# nano2_dps310.net
KiCad netlist of a schematic drawn in EAGLE
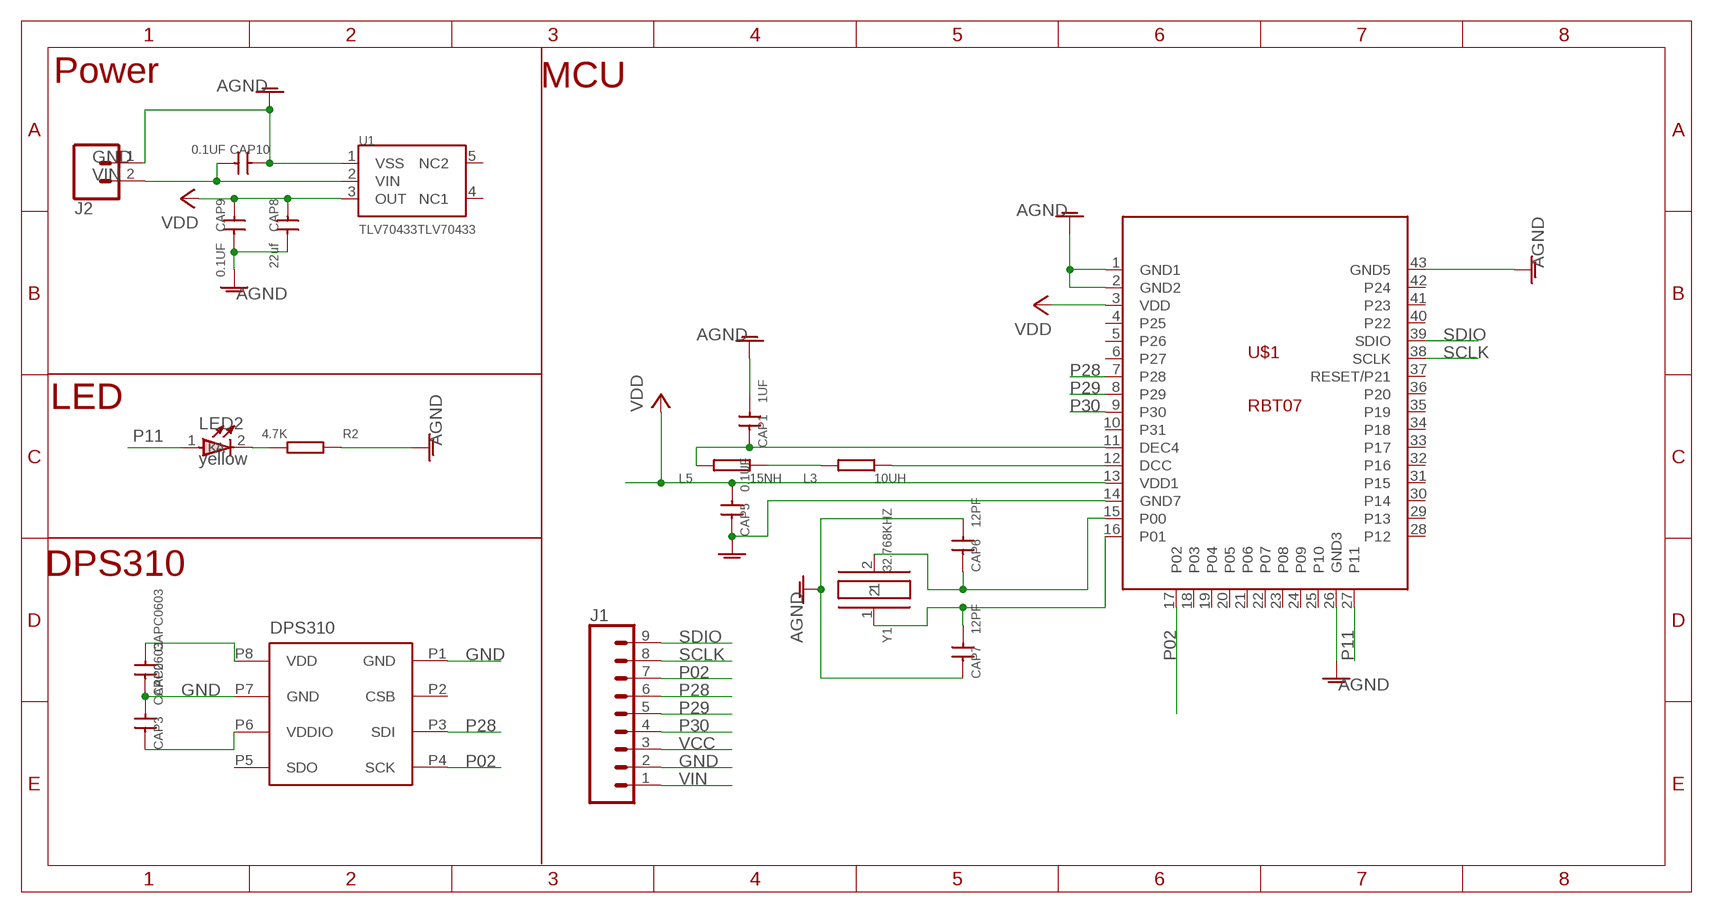
[diagram p0: schematic, sheet 1]

(export (version "E")
  (design (tool "Eeschema 10.0.6"))
  (components
    (comp (ref "CAP1")
      (value "1UF")
      (footprint "eagle-import:C-0402")
      (libsource (lib "eagle-import") (part "NANO2_CAP0402"))
    )
    (comp (ref "CAP2")
      (value "CAPC0603")
      (footprint "eagle-import:C0603")
      (libsource (lib "eagle-import") (part "CAPC0603"))
    )
    (comp (ref "CAP3")
      (value "CAPC0603")
      (footprint "eagle-import:C0603")
      (libsource (lib "eagle-import") (part "CAPC0603"))
    )
    (comp (ref "CAP5")
      (value "0.1UF")
      (footprint "eagle-import:C-0402")
      (libsource (lib "eagle-import") (part "NANO2_CAP0402"))
    )
    (comp (ref "CAP6")
      (value "12PF")
      (footprint "eagle-import:C-0402")
      (libsource (lib "eagle-import") (part "NANO2_CAP0402"))
    )
    (comp (ref "CAP7")
      (value "12PF")
      (footprint "eagle-import:C-0402")
      (libsource (lib "eagle-import") (part "NANO2_CAP0402"))
    )
    (comp (ref "CAP8")
      (value "22uf")
      (footprint "eagle-import:C0805")
      (libsource (lib "eagle-import") (part "NANO2_CAPC0805"))
    )
    (comp (ref "CAP9")
      (value "0.1UF")
      (footprint "eagle-import:C-0402")
      (libsource (lib "eagle-import") (part "NANO2_CAP0402"))
    )
    (comp (ref "CAP10")
      (value "0.1UF")
      (footprint "eagle-import:C-0402")
      (libsource (lib "eagle-import") (part "CAP0402"))
    )
    (comp (ref "J1")
      (value "CONN_09LOCK")
      (footprint "eagle-import:1X09_LOCK")
      (libsource (lib "eagle-import") (part "CONN_09LOCK"))
    )
    (comp (ref "J2")
      (value "CONN_02JST-PTH-2")
      (footprint "eagle-import:JST-2-PTH")
      (libsource (lib "eagle-import") (part "CONN_02JST-PTH-2"))
    )
    (comp (ref "L3")
      (value "10UH")
      (footprint "eagle-import:R0603")
      (libsource (lib "eagle-import") (part "RESR0603"))
    )
    (comp (ref "L5")
      (value "15NH")
      (footprint "eagle-import:R0402")
      (libsource (lib "eagle-import") (part "RESR0402"))
    )
    (comp (ref "LED2")
      (value "yellow")
      (footprint "eagle-import:LED0603")
      (libsource (lib "eagle-import") (part "LED"))
    )
    (comp (ref "R2")
      (value "4.7K")
      (footprint "eagle-import:R0402")
      (libsource (lib "eagle-import") (part "RESR0402"))
    )
    (comp (ref "U$1")
      (value "RBT07")
      (footprint "eagle-import:RBT07")
      (libsource (lib "eagle-import") (part "RBT07"))
    )
    (comp (ref "U1")
      (value "TLV70433TLV70433")
      (footprint "eagle-import:SOT-23-5")
      (fields (field (name "U1") "TLV70433DBVR"))
      (libsource (lib "eagle-import") (part "TLV70433TLV70433"))
    )
    (comp (ref "U2")
      (value "DPS310")
      (footprint "eagle-import:LGA-8")
      (libsource (lib "eagle-import") (part "DPS310"))
    )
    (comp (ref "Y1")
      (value "32.768KHZ")
      (footprint "eagle-import:CRY_3215")
      (libsource (lib "eagle-import") (part "CRY_32153215"))
    )
  )
  (nets
    (net (code "1") (name "/P02") (class "Default")
      (node (ref "J1") (pin "7") (pinfunction "7_7") (pintype "passive"))
      (node (ref "U$1") (pin "17") (pinfunction "P02_17") (pintype "bidirectional"))
      (node (ref "U2") (pin "P4") (pinfunction "SCK_P4") (pintype "bidirectional"))
    )
    (net (code "2") (name "/P11") (class "Default")
      (node (ref "LED2") (pin "1") (pinfunction "A_1") (pintype "bidirectional"))
      (node (ref "U$1") (pin "27") (pinfunction "P11_27") (pintype "bidirectional"))
    )
    (net (code "3") (name "/P28") (class "Default")
      (node (ref "J1") (pin "6") (pinfunction "6_6") (pintype "passive"))
      (node (ref "U$1") (pin "7") (pinfunction "P28_7") (pintype "bidirectional"))
      (node (ref "U2") (pin "P3") (pinfunction "SDI_P3") (pintype "bidirectional"))
    )
    (net (code "4") (name "/P29") (class "Default")
      (node (ref "J1") (pin "5") (pinfunction "5_5") (pintype "passive"))
      (node (ref "U$1") (pin "8") (pinfunction "P29_8") (pintype "bidirectional"))
    )
    (net (code "5") (name "/P30") (class "Default")
      (node (ref "J1") (pin "4") (pinfunction "4_4") (pintype "passive"))
      (node (ref "U$1") (pin "9") (pinfunction "P30_9") (pintype "bidirectional"))
    )
    (net (code "6") (name "/SCLK") (class "Default")
      (node (ref "J1") (pin "8") (pinfunction "8_8") (pintype "passive"))
      (node (ref "U$1") (pin "38") (pinfunction "SCLK_38") (pintype "bidirectional"))
    )
    (net (code "7") (name "/SDIO") (class "Default")
      (node (ref "J1") (pin "9") (pinfunction "9_9") (pintype "passive"))
      (node (ref "U$1") (pin "39") (pinfunction "SDIO_39") (pintype "bidirectional"))
    )
    (net (code "8") (name "/VIN") (class "Default")
      (node (ref "CAP10") (pin "1") (pinfunction "1_1") (pintype "bidirectional"))
      (node (ref "J1") (pin "1") (pinfunction "1_1") (pintype "passive"))
      (node (ref "J2") (pin "2") (pinfunction "2_2") (pintype "passive"))
      (node (ref "U1") (pin "2") (pinfunction "VIN_2") (pintype "bidirectional"))
    )
    (net (code "9") (name "AGND") (class "Default")
      (node (ref "CAP1") (pin "1") (pinfunction "1_1") (pintype "bidirectional"))
      (node (ref "CAP10") (pin "2") (pinfunction "2_2") (pintype "bidirectional"))
      (node (ref "CAP2") (pin "2") (pinfunction "2_2") (pintype "bidirectional"))
      (node (ref "CAP3") (pin "1") (pinfunction "1_1") (pintype "bidirectional"))
      (node (ref "CAP5") (pin "2") (pinfunction "2_2") (pintype "bidirectional"))
      (node (ref "CAP6") (pin "1") (pinfunction "1_1") (pintype "bidirectional"))
      (node (ref "CAP7") (pin "2") (pinfunction "2_2") (pintype "bidirectional"))
      (node (ref "CAP8") (pin "1") (pinfunction "1_1") (pintype "bidirectional"))
      (node (ref "CAP9") (pin "1") (pinfunction "1_1") (pintype "bidirectional"))
      (node (ref "J1") (pin "2") (pinfunction "2_2") (pintype "passive"))
      (node (ref "J2") (pin "1") (pinfunction "1_1") (pintype "passive"))
      (node (ref "R2") (pin "1") (pinfunction "1_1") (pintype "bidirectional"))
      (node (ref "U$1") (pin "1") (pinfunction "GND1_1") (pintype "bidirectional"))
      (node (ref "U$1") (pin "14") (pinfunction "GND7_14") (pintype "bidirectional"))
      (node (ref "U$1") (pin "2") (pinfunction "GND2_2") (pintype "bidirectional"))
      (node (ref "U$1") (pin "26") (pinfunction "GND3_26") (pintype "bidirectional"))
      (node (ref "U$1") (pin "43") (pinfunction "GND5_43") (pintype "bidirectional"))
      (node (ref "U1") (pin "1") (pinfunction "VSS_1") (pintype "bidirectional"))
      (node (ref "U2") (pin "P1") (pinfunction "GND_P1") (pintype "bidirectional"))
      (node (ref "U2") (pin "P7") (pinfunction "GND_P7") (pintype "bidirectional"))
    )
    (net (code "10") (name "Net-(L3-Pad1)") (class "Default")
      (node (ref "L3") (pin "1") (pinfunction "1_1") (pintype "bidirectional"))
      (node (ref "L5") (pin "2") (pinfunction "2_2") (pintype "bidirectional"))
    )
    (net (code "11") (name "Net-(LED2-K)") (class "Default")
      (node (ref "LED2") (pin "2") (pinfunction "K_2") (pintype "bidirectional"))
      (node (ref "R2") (pin "2") (pinfunction "2_2") (pintype "bidirectional"))
    )
    (net (code "12") (name "Net-(U$1-DCC)") (class "Default")
      (node (ref "L3") (pin "2") (pinfunction "2_2") (pintype "bidirectional"))
      (node (ref "U$1") (pin "12") (pinfunction "DCC_12") (pintype "bidirectional"))
    )
    (net (code "13") (name "Net-(U$1-DEC4)") (class "Default")
      (node (ref "CAP1") (pin "2") (pinfunction "2_2") (pintype "bidirectional"))
      (node (ref "L5") (pin "1") (pinfunction "1_1") (pintype "bidirectional"))
      (node (ref "U$1") (pin "11") (pinfunction "DEC4_11") (pintype "bidirectional"))
    )
    (net (code "14") (name "Net-(U$1-P00)") (class "Default")
      (node (ref "CAP6") (pin "2") (pinfunction "2_2") (pintype "bidirectional"))
      (node (ref "U$1") (pin "15") (pinfunction "P00_15") (pintype "bidirectional"))
      (node (ref "Y1") (pin "2") (pinfunction "2_2") (pintype "bidirectional"))
    )
    (net (code "15") (name "Net-(U$1-P01)") (class "Default")
      (node (ref "CAP7") (pin "1") (pinfunction "1_1") (pintype "bidirectional"))
      (node (ref "U$1") (pin "16") (pinfunction "P01_16") (pintype "bidirectional"))
      (node (ref "Y1") (pin "1") (pinfunction "1_1") (pintype "bidirectional"))
    )
    (net (code "16") (name "VDD") (class "Default")
      (node (ref "CAP2") (pin "1") (pinfunction "1_1") (pintype "bidirectional"))
      (node (ref "CAP3") (pin "2") (pinfunction "2_2") (pintype "bidirectional"))
      (node (ref "CAP5") (pin "1") (pinfunction "1_1") (pintype "bidirectional"))
      (node (ref "CAP8") (pin "2") (pinfunction "2_2") (pintype "bidirectional"))
      (node (ref "CAP9") (pin "2") (pinfunction "2_2") (pintype "bidirectional"))
      (node (ref "J1") (pin "3") (pinfunction "3_3") (pintype "passive"))
      (node (ref "U$1") (pin "13") (pinfunction "VDD1_13") (pintype "bidirectional"))
      (node (ref "U$1") (pin "3") (pinfunction "VDD_3") (pintype "bidirectional"))
      (node (ref "U1") (pin "3") (pinfunction "OUT_3") (pintype "bidirectional"))
      (node (ref "U2") (pin "P6") (pinfunction "VDDIO_P6") (pintype "bidirectional"))
      (node (ref "U2") (pin "P8") (pinfunction "VDD_P8") (pintype "bidirectional"))
    )
    (net (code "17") (name "unconnected-(U$1-P03-Pad18)") (class "Default")
      (node (ref "U$1") (pin "18") (pinfunction "P03_18") (pintype "bidirectional"))
    )
    (net (code "18") (name "unconnected-(U$1-P04-Pad19)") (class "Default")
      (node (ref "U$1") (pin "19") (pinfunction "P04_19") (pintype "bidirectional"))
    )
    (net (code "19") (name "unconnected-(U$1-P05-Pad20)") (class "Default")
      (node (ref "U$1") (pin "20") (pinfunction "P05_20") (pintype "bidirectional"))
    )
    (net (code "20") (name "unconnected-(U$1-P06-Pad21)") (class "Default")
      (node (ref "U$1") (pin "21") (pinfunction "P06_21") (pintype "bidirectional"))
    )
    (net (code "21") (name "unconnected-(U$1-P07-Pad22)") (class "Default")
      (node (ref "U$1") (pin "22") (pinfunction "P07_22") (pintype "bidirectional"))
    )
    (net (code "22") (name "unconnected-(U$1-P08-Pad23)") (class "Default")
      (node (ref "U$1") (pin "23") (pinfunction "P08_23") (pintype "bidirectional"))
    )
    (net (code "23") (name "unconnected-(U$1-P09-Pad24)") (class "Default")
      (node (ref "U$1") (pin "24") (pinfunction "P09_24") (pintype "bidirectional"))
    )
    (net (code "24") (name "unconnected-(U$1-P10-Pad25)") (class "Default")
      (node (ref "U$1") (pin "25") (pinfunction "P10_25") (pintype "bidirectional"))
    )
    (net (code "25") (name "unconnected-(U$1-P12-Pad28)") (class "Default")
      (node (ref "U$1") (pin "28") (pinfunction "P12_28") (pintype "bidirectional"))
    )
    (net (code "26") (name "unconnected-(U$1-P13-Pad29)") (class "Default")
      (node (ref "U$1") (pin "29") (pinfunction "P13_29") (pintype "bidirectional"))
    )
    (net (code "27") (name "unconnected-(U$1-P14-Pad30)") (class "Default")
      (node (ref "U$1") (pin "30") (pinfunction "P14_30") (pintype "bidirectional"))
    )
    (net (code "28") (name "unconnected-(U$1-P15-Pad31)") (class "Default")
      (node (ref "U$1") (pin "31") (pinfunction "P15_31") (pintype "bidirectional"))
    )
    (net (code "29") (name "unconnected-(U$1-P16-Pad32)") (class "Default")
      (node (ref "U$1") (pin "32") (pinfunction "P16_32") (pintype "bidirectional"))
    )
    (net (code "30") (name "unconnected-(U$1-P17-Pad33)") (class "Default")
      (node (ref "U$1") (pin "33") (pinfunction "P17_33") (pintype "bidirectional"))
    )
    (net (code "31") (name "unconnected-(U$1-P18-Pad34)") (class "Default")
      (node (ref "U$1") (pin "34") (pinfunction "P18_34") (pintype "bidirectional"))
    )
    (net (code "32") (name "unconnected-(U$1-P19-Pad35)") (class "Default")
      (node (ref "U$1") (pin "35") (pinfunction "P19_35") (pintype "bidirectional"))
    )
    (net (code "33") (name "unconnected-(U$1-P20-Pad36)") (class "Default")
      (node (ref "U$1") (pin "36") (pinfunction "P20_36") (pintype "bidirectional"))
    )
    (net (code "34") (name "unconnected-(U$1-P22-Pad40)") (class "Default")
      (node (ref "U$1") (pin "40") (pinfunction "P22_40") (pintype "bidirectional"))
    )
    (net (code "35") (name "unconnected-(U$1-P23-Pad41)") (class "Default")
      (node (ref "U$1") (pin "41") (pinfunction "P23_41") (pintype "bidirectional"))
    )
    (net (code "36") (name "unconnected-(U$1-P24-Pad42)") (class "Default")
      (node (ref "U$1") (pin "42") (pinfunction "P24_42") (pintype "bidirectional"))
    )
    (net (code "37") (name "unconnected-(U$1-P25-Pad4)") (class "Default")
      (node (ref "U$1") (pin "4") (pinfunction "P25_4") (pintype "bidirectional"))
    )
    (net (code "38") (name "unconnected-(U$1-P26-Pad5)") (class "Default")
      (node (ref "U$1") (pin "5") (pinfunction "P26_5") (pintype "bidirectional"))
    )
    (net (code "39") (name "unconnected-(U$1-P27-Pad6)") (class "Default")
      (node (ref "U$1") (pin "6") (pinfunction "P27_6") (pintype "bidirectional"))
    )
    (net (code "40") (name "unconnected-(U$1-P31-Pad10)") (class "Default")
      (node (ref "U$1") (pin "10") (pinfunction "P31_10") (pintype "bidirectional"))
    )
    (net (code "41") (name "unconnected-(U$1-RESET{slash}P21-Pad37)") (class "Default")
      (node (ref "U$1") (pin "37") (pinfunction "RESET/P21_37") (pintype "bidirectional"))
    )
    (net (code "42") (name "unconnected-(U1-NC1-Pad4)") (class "Default")
      (node (ref "U1") (pin "4") (pinfunction "NC1_4") (pintype "bidirectional"))
    )
    (net (code "43") (name "unconnected-(U1-NC2-Pad5)") (class "Default")
      (node (ref "U1") (pin "5") (pinfunction "NC2_5") (pintype "bidirectional"))
    )
    (net (code "44") (name "unconnected-(U2-CSB-PadP2)") (class "Default")
      (node (ref "U2") (pin "P2") (pinfunction "CSB_P2") (pintype "bidirectional"))
    )
    (net (code "45") (name "unconnected-(U2-SDO-PadP5)") (class "Default")
      (node (ref "U2") (pin "P5") (pinfunction "SDO_P5") (pintype "bidirectional"))
    )
  )
)
